# zero_shield.net
KiCad netlist of a schematic drawn in EAGLE
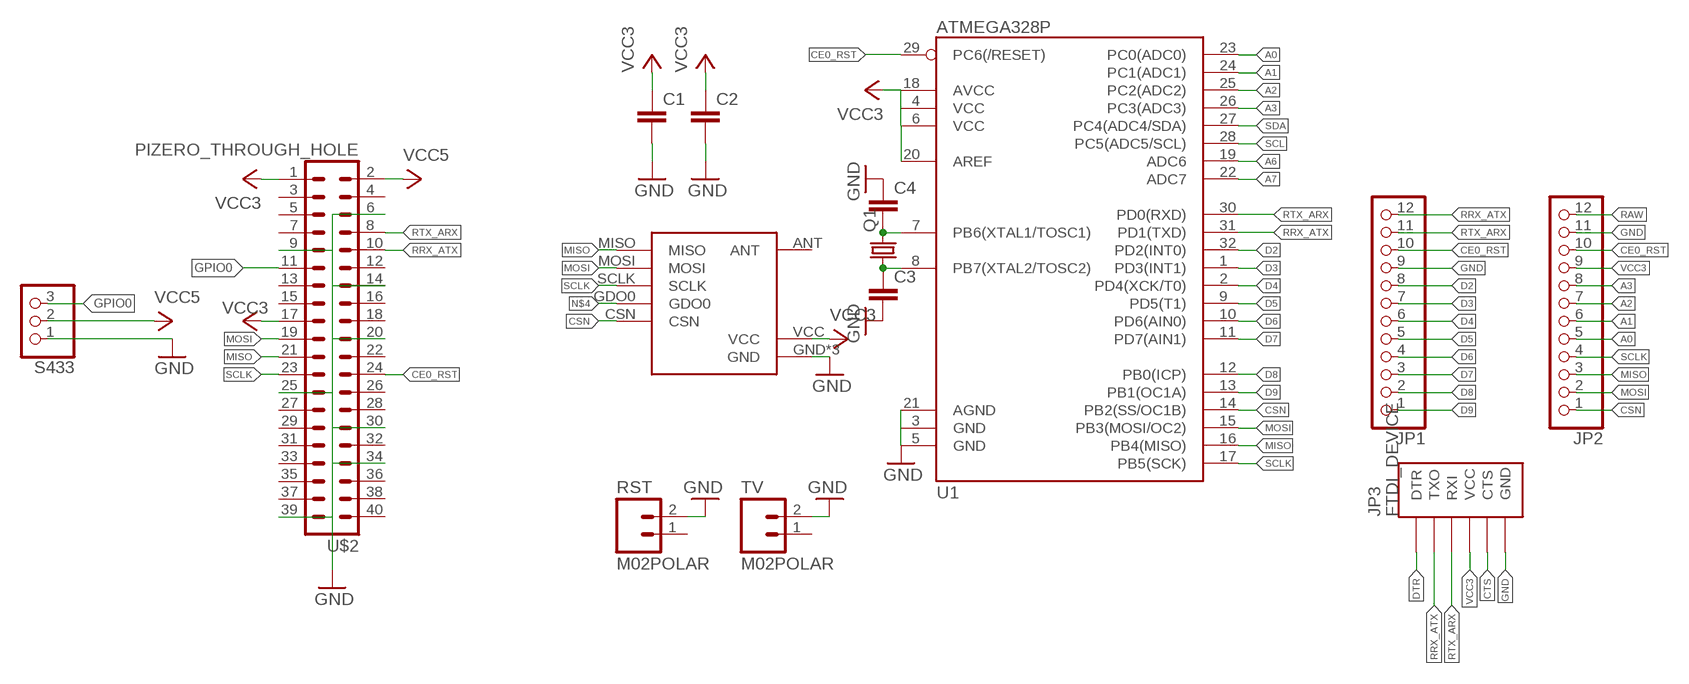
[diagram p0: schematic, sheet 1]

(export (version "E")
  (design (tool "Eeschema 10.0.6"))
  (components
    (comp (ref "C1")
      (value "C-EUC1206K")
      (footprint "eagle-import:C1206K")
      (libsource (lib "eagle-import") (part "C-EUC1206K"))
    )
    (comp (ref "C2")
      (value "C-EUC1206K")
      (footprint "eagle-import:C1206K")
      (libsource (lib "eagle-import") (part "C-EUC1206K"))
    )
    (comp (ref "C3")
      (value "C-EUC1206K")
      (footprint "eagle-import:C1206K")
      (libsource (lib "eagle-import") (part "C-EUC1206K"))
    )
    (comp (ref "C4")
      (value "C-EUC1206K")
      (footprint "eagle-import:C1206K")
      (libsource (lib "eagle-import") (part "C-EUC1206K"))
    )
    (comp (ref "JP1")
      (value "PINHD-1X12-CB")
      (footprint "eagle-import:1X12-CB")
      (libsource (lib "eagle-import") (part "PINHD-1X12-CB"))
    )
    (comp (ref "JP2")
      (value "PINHD-1X12-CB")
      (footprint "eagle-import:1X12-CB")
      (libsource (lib "eagle-import") (part "PINHD-1X12-CB"))
    )
    (comp (ref "JP3")
      (value "FTDI_DEVICE")
      (footprint "eagle-import:FTDI_DEVICE_SIDE")
      (libsource (lib "eagle-import") (part "FTDI_DEVICE"))
    )
    (comp (ref "Q1")
      (value "CRYSTALHC49S")
      (footprint "eagle-import:HC49_S")
      (libsource (lib "eagle-import") (part "CRYSTALHC49S"))
    )
    (comp (ref "RST")
      (value "M02POLAR")
      (footprint "eagle-import:MOLEX-1X2")
      (libsource (lib "eagle-import") (part "M02POLAR"))
    )
    (comp (ref "S433")
      (value "PINHD-1X3CB")
      (footprint "eagle-import:1X03-CLEANBIG")
      (libsource (lib "eagle-import") (part "PINHD-1X3CB"))
    )
    (comp (ref "TV")
      (value "M02POLAR")
      (footprint "eagle-import:MOLEX-1X2")
      (libsource (lib "eagle-import") (part "M02POLAR"))
    )
    (comp (ref "U$1")
      (value "CC1150BOARD")
      (footprint "eagle-import:CC1150BOARD")
      (libsource (lib "eagle-import") (part "CC1150BOARD"))
    )
    (comp (ref "U$2")
      (value "PIZERO_THROUGH_HOLE")
      (footprint "eagle-import:PIZERO_THOUGH_HOLE")
      (libsource (lib "eagle-import") (part "PIZERO_THROUGH_HOLE"))
    )
    (comp (ref "U1")
      (value "ATMEGA328P")
      (footprint "eagle-import:TQFP32-08")
      (libsource (lib "eagle-import") (part "ATMEGA328_SMT"))
    )
  )
  (nets
    (net (code "1") (name "A0") (class "Default")
      (node (ref "JP2") (pin "5") (pinfunction "5_5") (pintype "passive"))
      (node (ref "U1") (pin "23") (pinfunction "PC0(ADC0)_23") (pintype "bidirectional"))
    )
    (net (code "2") (name "A1") (class "Default")
      (node (ref "JP2") (pin "6") (pinfunction "6_6") (pintype "passive"))
      (node (ref "U1") (pin "24") (pinfunction "PC1(ADC1)_24") (pintype "bidirectional"))
    )
    (net (code "3") (name "A2") (class "Default")
      (node (ref "JP2") (pin "7") (pinfunction "7_7") (pintype "passive"))
      (node (ref "U1") (pin "25") (pinfunction "PC2(ADC2)_25") (pintype "bidirectional"))
    )
    (net (code "4") (name "A3") (class "Default")
      (node (ref "JP2") (pin "8") (pinfunction "8_8") (pintype "passive"))
      (node (ref "U1") (pin "26") (pinfunction "PC3(ADC3)_26") (pintype "bidirectional"))
    )
    (net (code "5") (name "A6") (class "Default")
      (node (ref "U1") (pin "19") (pinfunction "ADC6_19") (pintype "bidirectional"))
    )
    (net (code "6") (name "A7") (class "Default")
      (node (ref "U1") (pin "22") (pinfunction "ADC7_22") (pintype "bidirectional"))
    )
    (net (code "7") (name "CE0_RST") (class "Default")
      (node (ref "JP1") (pin "10") (pinfunction "10_10") (pintype "passive"))
      (node (ref "JP2") (pin "10") (pinfunction "10_10") (pintype "passive"))
      (node (ref "U$2") (pin "24") (pinfunction "24_24") (pintype "passive"))
      (node (ref "U1") (pin "29") (pinfunction "PC6(/RESET)_29") (pintype "bidirectional"))
    )
    (net (code "8") (name "CSN") (class "Default")
      (node (ref "JP2") (pin "1") (pinfunction "1_1") (pintype "passive"))
      (node (ref "U$1") (pin "CSN") (pinfunction "CSN_CSN") (pintype "bidirectional"))
      (node (ref "U1") (pin "14") (pinfunction "PB2(SS/OC1B)_14") (pintype "bidirectional"))
    )
    (net (code "9") (name "CTS") (class "Default")
      (node (ref "JP3") (pin "P$5") (pinfunction "CTS_P$5") (pintype "bidirectional"))
    )
    (net (code "10") (name "D2") (class "Default")
      (node (ref "JP1") (pin "8") (pinfunction "8_8") (pintype "passive"))
      (node (ref "U1") (pin "32") (pinfunction "PD2(INT0)_32") (pintype "bidirectional"))
    )
    (net (code "11") (name "D3") (class "Default")
      (node (ref "JP1") (pin "7") (pinfunction "7_7") (pintype "passive"))
      (node (ref "U1") (pin "1") (pinfunction "PD3(INT1)_1") (pintype "bidirectional"))
    )
    (net (code "12") (name "D4") (class "Default")
      (node (ref "JP1") (pin "6") (pinfunction "6_6") (pintype "passive"))
      (node (ref "U1") (pin "2") (pinfunction "PD4(XCK/T0)_2") (pintype "bidirectional"))
    )
    (net (code "13") (name "D5") (class "Default")
      (node (ref "JP1") (pin "5") (pinfunction "5_5") (pintype "passive"))
      (node (ref "U1") (pin "9") (pinfunction "PD5(T1)_9") (pintype "bidirectional"))
    )
    (net (code "14") (name "D6") (class "Default")
      (node (ref "JP1") (pin "4") (pinfunction "4_4") (pintype "passive"))
      (node (ref "U1") (pin "10") (pinfunction "PD6(AIN0)_10") (pintype "bidirectional"))
    )
    (net (code "15") (name "D7") (class "Default")
      (node (ref "JP1") (pin "3") (pinfunction "3_3") (pintype "passive"))
      (node (ref "U1") (pin "11") (pinfunction "PD7(AIN1)_11") (pintype "bidirectional"))
    )
    (net (code "16") (name "D8") (class "Default")
      (node (ref "JP1") (pin "2") (pinfunction "2_2") (pintype "passive"))
      (node (ref "U1") (pin "12") (pinfunction "PB0(ICP)_12") (pintype "bidirectional"))
    )
    (net (code "17") (name "D9") (class "Default")
      (node (ref "JP1") (pin "1") (pinfunction "1_1") (pintype "passive"))
      (node (ref "U1") (pin "13") (pinfunction "PB1(OC1A)_13") (pintype "bidirectional"))
    )
    (net (code "18") (name "DTR") (class "Default")
      (node (ref "JP3") (pin "P$1") (pinfunction "DTR_P$1") (pintype "bidirectional"))
    )
    (net (code "19") (name "GND") (class "Default")
      (node (ref "C1") (pin "2") (pinfunction "2_2") (pintype "passive"))
      (node (ref "C2") (pin "2") (pinfunction "2_2") (pintype "passive"))
      (node (ref "C3") (pin "2") (pinfunction "2_2") (pintype "passive"))
      (node (ref "C4") (pin "1") (pinfunction "1_1") (pintype "passive"))
      (node (ref "JP1") (pin "9") (pinfunction "9_9") (pintype "passive"))
      (node (ref "JP2") (pin "11") (pinfunction "11_11") (pintype "passive"))
      (node (ref "JP3") (pin "P$6") (pinfunction "GND_P$6") (pintype "bidirectional"))
      (node (ref "RST") (pin "2") (pinfunction "2_2") (pintype "passive"))
      (node (ref "S433") (pin "1") (pinfunction "1_1") (pintype "passive"))
      (node (ref "TV") (pin "2") (pinfunction "2_2") (pintype "passive"))
      (node (ref "U$1") (pin "GND") (pinfunction "GND_GND") (pintype "bidirectional"))
      (node (ref "U$1") (pin "GND2") (pinfunction "GND_GND2") (pintype "bidirectional"))
      (node (ref "U$1") (pin "GND3") (pinfunction "GND_GND3") (pintype "bidirectional"))
      (node (ref "U$2") (pin "14") (pinfunction "14_14") (pintype "passive"))
      (node (ref "U$2") (pin "20") (pinfunction "20_20") (pintype "passive"))
      (node (ref "U$2") (pin "25") (pinfunction "25_25") (pintype "passive"))
      (node (ref "U$2") (pin "30") (pinfunction "30_30") (pintype "passive"))
      (node (ref "U$2") (pin "34") (pinfunction "34_34") (pintype "passive"))
      (node (ref "U$2") (pin "39") (pinfunction "39_39") (pintype "passive"))
      (node (ref "U$2") (pin "6") (pinfunction "6_6") (pintype "passive"))
      (node (ref "U$2") (pin "9") (pinfunction "9_9") (pintype "passive"))
      (node (ref "U1") (pin "21") (pinfunction "AGND_21") (pintype "bidirectional"))
      (node (ref "U1") (pin "3") (pinfunction "GND_3") (pintype "bidirectional"))
      (node (ref "U1") (pin "5") (pinfunction "GND_5") (pintype "bidirectional"))
    )
    (net (code "20") (name "GPIO0") (class "Default")
      (node (ref "S433") (pin "3") (pinfunction "3_3") (pintype "passive"))
      (node (ref "U$2") (pin "11") (pinfunction "11_11") (pintype "passive"))
    )
    (net (code "21") (name "MISO") (class "Default")
      (node (ref "JP2") (pin "3") (pinfunction "3_3") (pintype "passive"))
      (node (ref "U$1") (pin "MISO") (pinfunction "MISO_MISO") (pintype "bidirectional"))
      (node (ref "U$2") (pin "21") (pinfunction "21_21") (pintype "passive"))
      (node (ref "U1") (pin "16") (pinfunction "PB4(MISO)_16") (pintype "bidirectional"))
    )
    (net (code "22") (name "MOSI") (class "Default")
      (node (ref "JP2") (pin "2") (pinfunction "2_2") (pintype "passive"))
      (node (ref "U$1") (pin "MOSI") (pinfunction "MOSI_MOSI") (pintype "bidirectional"))
      (node (ref "U$2") (pin "19") (pinfunction "19_19") (pintype "passive"))
      (node (ref "U1") (pin "15") (pinfunction "PB3(MOSI/OC2)_15") (pintype "bidirectional"))
    )
    (net (code "23") (name "N$4") (class "Default")
      (node (ref "U$1") (pin "GDO0") (pinfunction "GDO0_GDO0") (pintype "bidirectional"))
    )
    (net (code "24") (name "Net-(U1-PB6(XTAL1{slash}TOSC1))") (class "Default")
      (node (ref "C4") (pin "2") (pinfunction "2_2") (pintype "passive"))
      (node (ref "Q1") (pin "2") (pinfunction "2_2") (pintype "passive"))
      (node (ref "U1") (pin "7") (pinfunction "PB6(XTAL1/TOSC1)_7") (pintype "bidirectional"))
    )
    (net (code "25") (name "Net-(U1-PB7(XTAL2{slash}TOSC2))") (class "Default")
      (node (ref "C3") (pin "1") (pinfunction "1_1") (pintype "passive"))
      (node (ref "Q1") (pin "1") (pinfunction "1_1") (pintype "passive"))
      (node (ref "U1") (pin "8") (pinfunction "PB7(XTAL2/TOSC2)_8") (pintype "bidirectional"))
    )
    (net (code "26") (name "RAW") (class "Default")
      (node (ref "JP2") (pin "12") (pinfunction "12_12") (pintype "passive"))
    )
    (net (code "27") (name "RRX_ATX") (class "Default")
      (node (ref "JP1") (pin "12") (pinfunction "12_12") (pintype "passive"))
      (node (ref "JP3") (pin "P$2") (pinfunction "TXO_P$2") (pintype "bidirectional"))
      (node (ref "U$2") (pin "10") (pinfunction "10_10") (pintype "passive"))
      (node (ref "U1") (pin "31") (pinfunction "PD1(TXD)_31") (pintype "bidirectional"))
    )
    (net (code "28") (name "RTX_ARX") (class "Default")
      (node (ref "JP1") (pin "11") (pinfunction "11_11") (pintype "passive"))
      (node (ref "JP3") (pin "P$3") (pinfunction "RXI_P$3") (pintype "bidirectional"))
      (node (ref "U$2") (pin "8") (pinfunction "8_8") (pintype "passive"))
      (node (ref "U1") (pin "30") (pinfunction "PD0(RXD)_30") (pintype "bidirectional"))
    )
    (net (code "29") (name "SCL") (class "Default")
      (node (ref "U1") (pin "28") (pinfunction "PC5(ADC5/SCL)_28") (pintype "bidirectional"))
    )
    (net (code "30") (name "SCLK") (class "Default")
      (node (ref "JP2") (pin "4") (pinfunction "4_4") (pintype "passive"))
      (node (ref "U$1") (pin "SCLK") (pinfunction "SCLK_SCLK") (pintype "bidirectional"))
      (node (ref "U$2") (pin "23") (pinfunction "23_23") (pintype "passive"))
      (node (ref "U1") (pin "17") (pinfunction "PB5(SCK)_17") (pintype "bidirectional"))
    )
    (net (code "31") (name "SDA") (class "Default")
      (node (ref "U1") (pin "27") (pinfunction "PC4(ADC4/SDA)_27") (pintype "bidirectional"))
    )
    (net (code "32") (name "VCC3") (class "Default")
      (node (ref "C1") (pin "1") (pinfunction "1_1") (pintype "passive"))
      (node (ref "C2") (pin "1") (pinfunction "1_1") (pintype "passive"))
      (node (ref "JP2") (pin "9") (pinfunction "9_9") (pintype "passive"))
      (node (ref "JP3") (pin "P$4") (pinfunction "VCC_P$4") (pintype "bidirectional"))
      (node (ref "U$1") (pin "VCC") (pinfunction "VCC_VCC") (pintype "bidirectional"))
      (node (ref "U$2") (pin "1") (pinfunction "1_1") (pintype "passive"))
      (node (ref "U$2") (pin "17") (pinfunction "17_17") (pintype "passive"))
      (node (ref "U1") (pin "18") (pinfunction "AVCC_18") (pintype "bidirectional"))
      (node (ref "U1") (pin "20") (pinfunction "AREF_20") (pintype "bidirectional"))
      (node (ref "U1") (pin "4") (pinfunction "VCC_4") (pintype "bidirectional"))
      (node (ref "U1") (pin "6") (pinfunction "VCC_6") (pintype "bidirectional"))
    )
    (net (code "33") (name "VCC5") (class "Default")
      (node (ref "S433") (pin "2") (pinfunction "2_2") (pintype "passive"))
      (node (ref "U$2") (pin "2") (pinfunction "2_2") (pintype "passive"))
    )
    (net (code "34") (name "unconnected-(RST-Pad1)") (class "Default")
      (node (ref "RST") (pin "1") (pinfunction "1_1") (pintype "passive"))
    )
    (net (code "35") (name "unconnected-(TV-Pad1)") (class "Default")
      (node (ref "TV") (pin "1") (pinfunction "1_1") (pintype "passive"))
    )
    (net (code "36") (name "unconnected-(U$1-PadANT)") (class "Default")
      (node (ref "U$1") (pin "ANT") (pinfunction "ANT_ANT") (pintype "bidirectional"))
    )
    (net (code "37") (name "unconnected-(U$2-Pad3)") (class "Default")
      (node (ref "U$2") (pin "3") (pinfunction "3_3") (pintype "passive"))
    )
    (net (code "38") (name "unconnected-(U$2-Pad4)") (class "Default")
      (node (ref "U$2") (pin "4") (pinfunction "4_4") (pintype "passive"))
    )
    (net (code "39") (name "unconnected-(U$2-Pad5)") (class "Default")
      (node (ref "U$2") (pin "5") (pinfunction "5_5") (pintype "passive"))
    )
    (net (code "40") (name "unconnected-(U$2-Pad7)") (class "Default")
      (node (ref "U$2") (pin "7") (pinfunction "7_7") (pintype "passive"))
    )
    (net (code "41") (name "unconnected-(U$2-Pad12)") (class "Default")
      (node (ref "U$2") (pin "12") (pinfunction "12_12") (pintype "passive"))
    )
    (net (code "42") (name "unconnected-(U$2-Pad13)") (class "Default")
      (node (ref "U$2") (pin "13") (pinfunction "13_13") (pintype "passive"))
    )
    (net (code "43") (name "unconnected-(U$2-Pad15)") (class "Default")
      (node (ref "U$2") (pin "15") (pinfunction "15_15") (pintype "passive"))
    )
    (net (code "44") (name "unconnected-(U$2-Pad16)") (class "Default")
      (node (ref "U$2") (pin "16") (pinfunction "16_16") (pintype "passive"))
    )
    (net (code "45") (name "unconnected-(U$2-Pad18)") (class "Default")
      (node (ref "U$2") (pin "18") (pinfunction "18_18") (pintype "passive"))
    )
    (net (code "46") (name "unconnected-(U$2-Pad22)") (class "Default")
      (node (ref "U$2") (pin "22") (pinfunction "22_22") (pintype "passive"))
    )
    (net (code "47") (name "unconnected-(U$2-Pad26)") (class "Default")
      (node (ref "U$2") (pin "26") (pinfunction "26_26") (pintype "passive"))
    )
    (net (code "48") (name "unconnected-(U$2-Pad27)") (class "Default")
      (node (ref "U$2") (pin "27") (pinfunction "27_27") (pintype "passive"))
    )
    (net (code "49") (name "unconnected-(U$2-Pad28)") (class "Default")
      (node (ref "U$2") (pin "28") (pinfunction "28_28") (pintype "passive"))
    )
    (net (code "50") (name "unconnected-(U$2-Pad29)") (class "Default")
      (node (ref "U$2") (pin "29") (pinfunction "29_29") (pintype "passive"))
    )
    (net (code "51") (name "unconnected-(U$2-Pad31)") (class "Default")
      (node (ref "U$2") (pin "31") (pinfunction "31_31") (pintype "passive"))
    )
    (net (code "52") (name "unconnected-(U$2-Pad32)") (class "Default")
      (node (ref "U$2") (pin "32") (pinfunction "32_32") (pintype "passive"))
    )
    (net (code "53") (name "unconnected-(U$2-Pad33)") (class "Default")
      (node (ref "U$2") (pin "33") (pinfunction "33_33") (pintype "passive"))
    )
    (net (code "54") (name "unconnected-(U$2-Pad35)") (class "Default")
      (node (ref "U$2") (pin "35") (pinfunction "35_35") (pintype "passive"))
    )
    (net (code "55") (name "unconnected-(U$2-Pad36)") (class "Default")
      (node (ref "U$2") (pin "36") (pinfunction "36_36") (pintype "passive"))
    )
    (net (code "56") (name "unconnected-(U$2-Pad37)") (class "Default")
      (node (ref "U$2") (pin "37") (pinfunction "37_37") (pintype "passive"))
    )
    (net (code "57") (name "unconnected-(U$2-Pad38)") (class "Default")
      (node (ref "U$2") (pin "38") (pinfunction "38_38") (pintype "passive"))
    )
    (net (code "58") (name "unconnected-(U$2-Pad40)") (class "Default")
      (node (ref "U$2") (pin "40") (pinfunction "40_40") (pintype "passive"))
    )
  )
)
